# flashlight.net
KiCad netlist of a schematic drawn in EAGLE
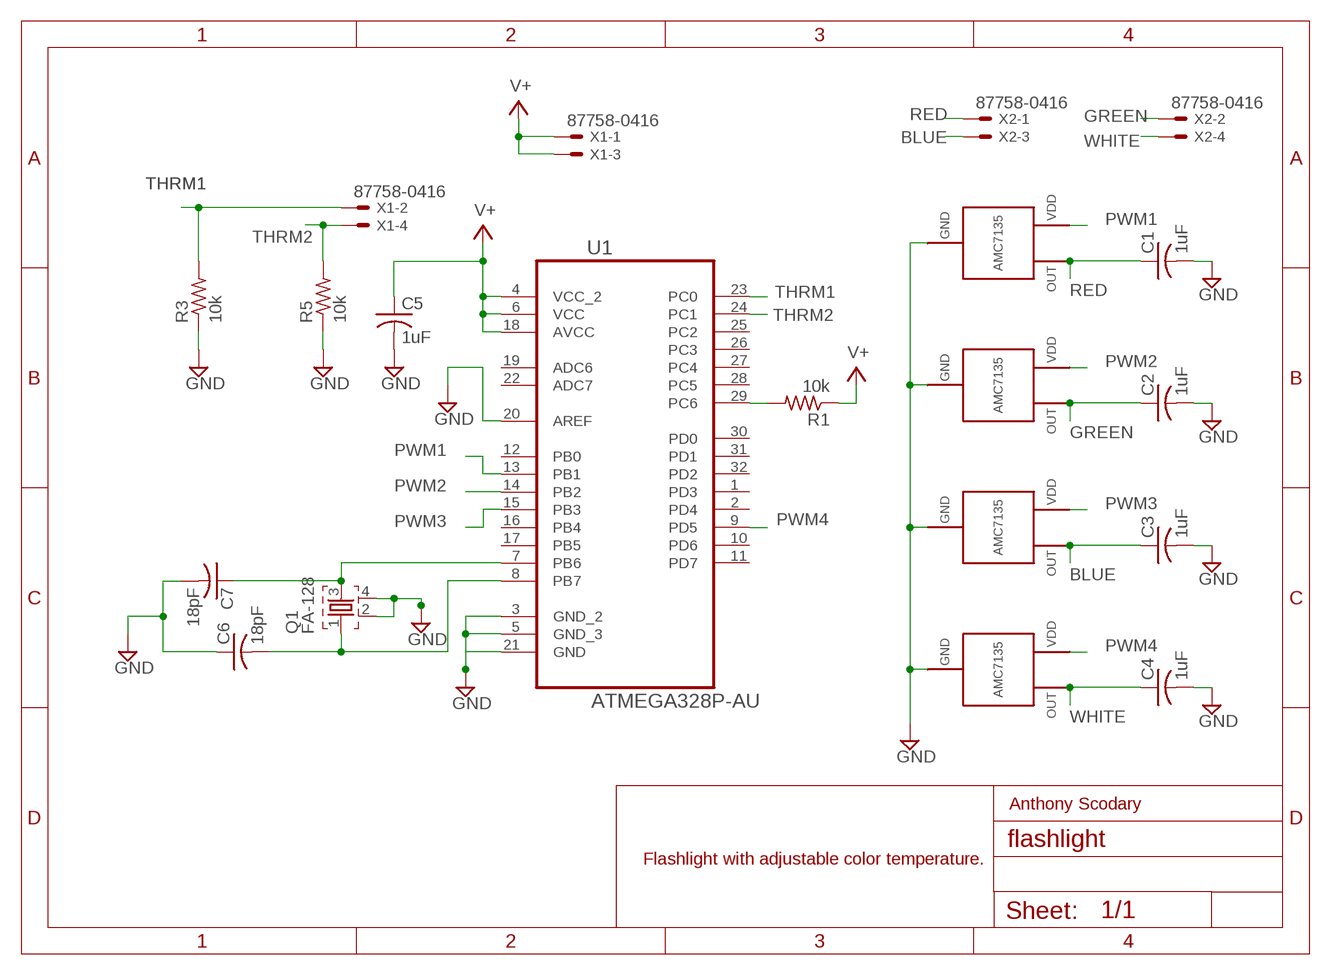
[diagram p0: schematic, sheet 1]

(export (version "E")
  (design (tool "Eeschema 10.0.6"))
  (components
    (comp (ref "C1")
      (value "1uF")
      (footprint "eagle-import:C0805")
      (libsource (lib "eagle-import") (part "C-USC0805"))
    )
    (comp (ref "C2")
      (value "1uF")
      (footprint "eagle-import:C0805")
      (libsource (lib "eagle-import") (part "C-USC0805"))
    )
    (comp (ref "C3")
      (value "1uF")
      (footprint "eagle-import:C0805")
      (libsource (lib "eagle-import") (part "C-USC0805"))
    )
    (comp (ref "C4")
      (value "1uF")
      (footprint "eagle-import:C0805")
      (libsource (lib "eagle-import") (part "C-USC0805"))
    )
    (comp (ref "C5")
      (value "1uF")
      (footprint "eagle-import:C0805")
      (libsource (lib "eagle-import") (part "C-USC0805"))
    )
    (comp (ref "C6")
      (value "18pF")
      (footprint "eagle-import:C0805")
      (libsource (lib "eagle-import") (part "C-USC0805"))
    )
    (comp (ref "C7")
      (value "18pF")
      (footprint "eagle-import:C0805")
      (libsource (lib "eagle-import") (part "C-USC0805"))
    )
    (comp (ref "Q1")
      (value "FA-128")
      (footprint "eagle-import:FA-128")
      (libsource (lib "eagle-import") (part "FA-128"))
    )
    (comp (ref "R1")
      (value "10k")
      (footprint "eagle-import:R0805")
      (libsource (lib "eagle-import") (part "R-US_R0805"))
    )
    (comp (ref "R3")
      (value "10k")
      (footprint "eagle-import:R0805")
      (libsource (lib "eagle-import") (part "R-US_R0805"))
    )
    (comp (ref "R5")
      (value "10k")
      (footprint "eagle-import:R0805")
      (libsource (lib "eagle-import") (part "R-US_R0805"))
    )
    (comp (ref "U$1")
      (value "AMC7135_CC_REGULATOR")
      (footprint "eagle-import:AMC7135_CC_REGULATOR")
      (libsource (lib "eagle-import") (part "AMC7135_CC_REGULATOR"))
    )
    (comp (ref "U$2")
      (value "AMC7135_CC_REGULATOR")
      (footprint "eagle-import:AMC7135_CC_REGULATOR")
      (libsource (lib "eagle-import") (part "AMC7135_CC_REGULATOR"))
    )
    (comp (ref "U$3")
      (value "AMC7135_CC_REGULATOR")
      (footprint "eagle-import:AMC7135_CC_REGULATOR")
      (libsource (lib "eagle-import") (part "AMC7135_CC_REGULATOR"))
    )
    (comp (ref "U$4")
      (value "AMC7135_CC_REGULATOR")
      (footprint "eagle-import:AMC7135_CC_REGULATOR")
      (libsource (lib "eagle-import") (part "AMC7135_CC_REGULATOR"))
    )
    (comp (ref "U1")
      (value "ATMEGA328P-AU")
      (footprint "eagle-import:QFP80P900X900X120-32N")
      (libsource (lib "eagle-import") (part "ATMEGA328P-AU"))
    )
    (comp (ref "X1")
      (value "87758-0416")
      (footprint "eagle-import:87758-0416")
      (fields (field (name "MF") "FARNELL"))
      (libsource (lib "eagle-import") (part "87758-0416"))
    )
    (comp (ref "X2")
      (value "87758-0416")
      (footprint "eagle-import:87758-0416")
      (fields (field (name "MF") "FARNELL"))
      (libsource (lib "eagle-import") (part "87758-0416"))
    )
  )
  (nets
    (net (code "1") (name "/BLUE") (class "Default")
      (node (ref "C3") (pin "1") (pinfunction "1_1") (pintype "passive"))
      (node (ref "U$3") (pin "OUT") (pinfunction "OUT_OUT") (pintype "bidirectional"))
      (node (ref "X2") (pin "3") (pinfunction "S_3") (pintype "passive"))
    )
    (net (code "2") (name "/GREEN") (class "Default")
      (node (ref "C2") (pin "1") (pinfunction "1_1") (pintype "passive"))
      (node (ref "U$2") (pin "OUT") (pinfunction "OUT_OUT") (pintype "bidirectional"))
      (node (ref "X2") (pin "2") (pinfunction "S_2") (pintype "passive"))
    )
    (net (code "3") (name "/PWM1") (class "Default")
      (node (ref "U$1") (pin "VDD") (pinfunction "VDD_VDD") (pintype "bidirectional"))
      (node (ref "U1") (pin "13") (pinfunction "PB1_13") (pintype "bidirectional"))
    )
    (net (code "4") (name "/PWM2") (class "Default")
      (node (ref "U$2") (pin "VDD") (pinfunction "VDD_VDD") (pintype "bidirectional"))
      (node (ref "U1") (pin "14") (pinfunction "PB2_14") (pintype "bidirectional"))
    )
    (net (code "5") (name "/PWM3") (class "Default")
      (node (ref "U$3") (pin "VDD") (pinfunction "VDD_VDD") (pintype "bidirectional"))
      (node (ref "U1") (pin "15") (pinfunction "PB3_15") (pintype "bidirectional"))
    )
    (net (code "6") (name "/PWM4") (class "Default")
      (node (ref "U$4") (pin "VDD") (pinfunction "VDD_VDD") (pintype "bidirectional"))
      (node (ref "U1") (pin "9") (pinfunction "PD5_9") (pintype "bidirectional"))
    )
    (net (code "7") (name "/RED") (class "Default")
      (node (ref "C1") (pin "1") (pinfunction "1_1") (pintype "passive"))
      (node (ref "U$1") (pin "OUT") (pinfunction "OUT_OUT") (pintype "bidirectional"))
      (node (ref "X2") (pin "1") (pinfunction "S_1") (pintype "passive"))
    )
    (net (code "8") (name "/THRM1") (class "Default")
      (node (ref "R3") (pin "2") (pinfunction "2_2") (pintype "passive"))
      (node (ref "U1") (pin "23") (pinfunction "PC0_23") (pintype "bidirectional"))
      (node (ref "X1") (pin "2") (pinfunction "S_2") (pintype "passive"))
    )
    (net (code "9") (name "/THRM2") (class "Default")
      (node (ref "R5") (pin "2") (pinfunction "2_2") (pintype "passive"))
      (node (ref "U1") (pin "24") (pinfunction "PC1_24") (pintype "bidirectional"))
      (node (ref "X1") (pin "4") (pinfunction "S_4") (pintype "passive"))
    )
    (net (code "10") (name "/WHITE") (class "Default")
      (node (ref "C4") (pin "1") (pinfunction "1_1") (pintype "passive"))
      (node (ref "U$4") (pin "OUT") (pinfunction "OUT_OUT") (pintype "bidirectional"))
      (node (ref "X2") (pin "4") (pinfunction "S_4") (pintype "passive"))
    )
    (net (code "11") (name "GND") (class "Default")
      (node (ref "C1") (pin "2") (pinfunction "2_2") (pintype "passive"))
      (node (ref "C2") (pin "2") (pinfunction "2_2") (pintype "passive"))
      (node (ref "C3") (pin "2") (pinfunction "2_2") (pintype "passive"))
      (node (ref "C4") (pin "2") (pinfunction "2_2") (pintype "passive"))
      (node (ref "C5") (pin "2") (pinfunction "2_2") (pintype "passive"))
      (node (ref "C6") (pin "1") (pinfunction "1_1") (pintype "passive"))
      (node (ref "C7") (pin "2") (pinfunction "2_2") (pintype "passive"))
      (node (ref "Q1") (pin "2") (pinfunction "2_2") (pintype "passive"))
      (node (ref "Q1") (pin "4") (pinfunction "4_4") (pintype "passive"))
      (node (ref "R3") (pin "1") (pinfunction "1_1") (pintype "passive"))
      (node (ref "R5") (pin "1") (pinfunction "1_1") (pintype "passive"))
      (node (ref "U$1") (pin "GND2") (pinfunction "GND_GND2") (pintype "bidirectional"))
      (node (ref "U$1") (pin "GND3") (pinfunction "GND_GND3") (pintype "bidirectional"))
      (node (ref "U$2") (pin "GND2") (pinfunction "GND_GND2") (pintype "bidirectional"))
      (node (ref "U$2") (pin "GND3") (pinfunction "GND_GND3") (pintype "bidirectional"))
      (node (ref "U$3") (pin "GND2") (pinfunction "GND_GND2") (pintype "bidirectional"))
      (node (ref "U$3") (pin "GND3") (pinfunction "GND_GND3") (pintype "bidirectional"))
      (node (ref "U$4") (pin "GND2") (pinfunction "GND_GND2") (pintype "bidirectional"))
      (node (ref "U$4") (pin "GND3") (pinfunction "GND_GND3") (pintype "bidirectional"))
      (node (ref "U1") (pin "20") (pinfunction "AREF_20") (pintype "input"))
      (node (ref "U1") (pin "21") (pinfunction "GND_21") (pintype "passive"))
      (node (ref "U1") (pin "3") (pinfunction "GND_2_3") (pintype "passive"))
      (node (ref "U1") (pin "5") (pinfunction "GND_3_5") (pintype "passive"))
    )
    (net (code "12") (name "Net-(U1-PB6)") (class "Default")
      (node (ref "C7") (pin "1") (pinfunction "1_1") (pintype "passive"))
      (node (ref "Q1") (pin "3") (pinfunction "3_3") (pintype "passive"))
      (node (ref "U1") (pin "7") (pinfunction "PB6_7") (pintype "bidirectional"))
    )
    (net (code "13") (name "Net-(U1-PB7)") (class "Default")
      (node (ref "C6") (pin "2") (pinfunction "2_2") (pintype "passive"))
      (node (ref "Q1") (pin "1") (pinfunction "1_1") (pintype "passive"))
      (node (ref "U1") (pin "8") (pinfunction "PB7_8") (pintype "bidirectional"))
    )
    (net (code "14") (name "Net-(U1-PC6)") (class "Default")
      (node (ref "R1") (pin "2") (pinfunction "2_2") (pintype "passive"))
      (node (ref "U1") (pin "29") (pinfunction "PC6_29") (pintype "bidirectional"))
    )
    (net (code "15") (name "V+") (class "Default")
      (node (ref "C5") (pin "1") (pinfunction "1_1") (pintype "passive"))
      (node (ref "R1") (pin "1") (pinfunction "1_1") (pintype "passive"))
      (node (ref "U1") (pin "18") (pinfunction "AVCC_18") (pintype "power_in"))
      (node (ref "U1") (pin "4") (pinfunction "VCC_2_4") (pintype "power_in"))
      (node (ref "U1") (pin "6") (pinfunction "VCC_6") (pintype "power_in"))
      (node (ref "X1") (pin "1") (pinfunction "S_1") (pintype "passive"))
      (node (ref "X1") (pin "3") (pinfunction "S_3") (pintype "passive"))
    )
    (net (code "16") (name "unconnected-(U1-ADC6-Pad19)") (class "Default")
      (node (ref "U1") (pin "19") (pinfunction "ADC6_19") (pintype "input"))
    )
    (net (code "17") (name "unconnected-(U1-ADC7-Pad22)") (class "Default")
      (node (ref "U1") (pin "22") (pinfunction "ADC7_22") (pintype "input"))
    )
    (net (code "18") (name "unconnected-(U1-PB0-Pad12)") (class "Default")
      (node (ref "U1") (pin "12") (pinfunction "PB0_12") (pintype "bidirectional"))
    )
    (net (code "19") (name "unconnected-(U1-PB4-Pad16)") (class "Default")
      (node (ref "U1") (pin "16") (pinfunction "PB4_16") (pintype "bidirectional"))
    )
    (net (code "20") (name "unconnected-(U1-PB5-Pad17)") (class "Default")
      (node (ref "U1") (pin "17") (pinfunction "PB5_17") (pintype "bidirectional"))
    )
    (net (code "21") (name "unconnected-(U1-PC2-Pad25)") (class "Default")
      (node (ref "U1") (pin "25") (pinfunction "PC2_25") (pintype "bidirectional"))
    )
    (net (code "22") (name "unconnected-(U1-PC3-Pad26)") (class "Default")
      (node (ref "U1") (pin "26") (pinfunction "PC3_26") (pintype "bidirectional"))
    )
    (net (code "23") (name "unconnected-(U1-PC4-Pad27)") (class "Default")
      (node (ref "U1") (pin "27") (pinfunction "PC4_27") (pintype "bidirectional"))
    )
    (net (code "24") (name "unconnected-(U1-PC5-Pad28)") (class "Default")
      (node (ref "U1") (pin "28") (pinfunction "PC5_28") (pintype "bidirectional"))
    )
    (net (code "25") (name "unconnected-(U1-PD0-Pad30)") (class "Default")
      (node (ref "U1") (pin "30") (pinfunction "PD0_30") (pintype "bidirectional"))
    )
    (net (code "26") (name "unconnected-(U1-PD1-Pad31)") (class "Default")
      (node (ref "U1") (pin "31") (pinfunction "PD1_31") (pintype "bidirectional"))
    )
    (net (code "27") (name "unconnected-(U1-PD2-Pad32)") (class "Default")
      (node (ref "U1") (pin "32") (pinfunction "PD2_32") (pintype "bidirectional"))
    )
    (net (code "28") (name "unconnected-(U1-PD3-Pad1)") (class "Default")
      (node (ref "U1") (pin "1") (pinfunction "PD3_1") (pintype "bidirectional"))
    )
    (net (code "29") (name "unconnected-(U1-PD4-Pad2)") (class "Default")
      (node (ref "U1") (pin "2") (pinfunction "PD4_2") (pintype "bidirectional"))
    )
    (net (code "30") (name "unconnected-(U1-PD6-Pad10)") (class "Default")
      (node (ref "U1") (pin "10") (pinfunction "PD6_10") (pintype "bidirectional"))
    )
    (net (code "31") (name "unconnected-(U1-PD7-Pad11)") (class "Default")
      (node (ref "U1") (pin "11") (pinfunction "PD7_11") (pintype "bidirectional"))
    )
  )
)
